# Protect.net
KiCad netlist of a schematic drawn in Altium Designer
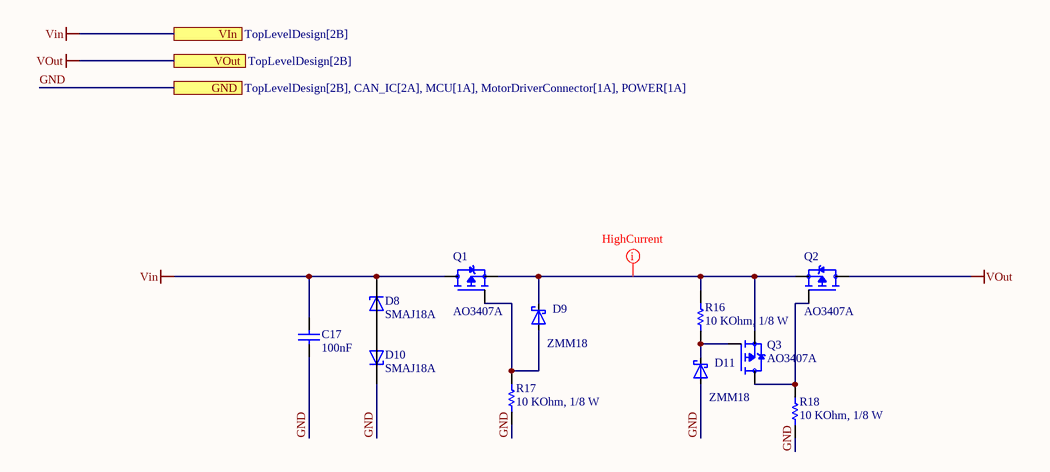
[diagram p0: Protect.SchDoc]

(export (version "E")
  (design (tool "Eeschema 10.0.6"))
  (components
    (comp (ref "C17")
      (value "100nF")
      (footprint "CAP_0805")
      (description "CAP, size 0805, 0.1 nF, 50 VDC")
      (fields
        (field (name "TOLERANCE") "10%")
        (field (name "Comment") "0108051041050")
        (field (name "SOURCE") "Capacitor_0805_10_percent.SchLib")
      )
      (libsource (lib "Tin Tran") (part "0108056841050"))
    )
    (comp (ref "D8")
      (value "SMAJ18A")
      (footprint "DIOM4325X250N")
      (description "400W, 21.1V, 5%, Unidirectional, TVS")
      (fields (field (name "MF") "Taiwan Semiconductor"))
      (libsource (lib "Tin Tran") (part "SMAJ18A"))
    )
    (comp (ref "D9")
      (value "ZMM18")
      (footprint "SOD-80_MiniMELF_Glass")
      (libsource (lib "Tin Tran") (part "Schottky-Diode"))
    )
    (comp (ref "D10")
      (value "SMAJ18A")
      (footprint "DIOM4325X250N")
      (description "400W, 21.1V, 5%, Unidirectional, TVS")
      (fields (field (name "MF") "Taiwan Semiconductor"))
      (libsource (lib "Tin Tran") (part "SMAJ18A"))
    )
    (comp (ref "D11")
      (value "ZMM18")
      (footprint "SOD-80_MiniMELF_Glass")
      (libsource (lib "Tin Tran") (part "Schottky-Diode"))
    )
    (comp (ref "Q1")
      (value "AO3407A")
      (footprint "SOT95P280X125-3N")
      (description "P-Channel 30 V 4.3A (Ta) 1.4W (Ta) Surface Mount SOT-23-3")
      (fields (field (name "MF") "Alpha &"))
      (libsource (lib "Tin Tran") (part "AO3407A"))
    )
    (comp (ref "Q2")
      (value "AO3407A")
      (footprint "SOT95P280X125-3N")
      (description "P-Channel 30 V 4.3A (Ta) 1.4W (Ta) Surface Mount SOT-23-3")
      (fields (field (name "MF") "Alpha &"))
      (libsource (lib "Tin Tran") (part "AO3407A"))
    )
    (comp (ref "Q3")
      (value "AO3407A")
      (footprint "SOT95P280X125-3N")
      (description "P-Channel 30 V 4.3A (Ta) 1.4W (Ta) Surface Mount SOT-23-3")
      (fields (field (name "MF") "Alpha &"))
      (libsource (lib "Tin Tran") (part "AO3407A"))
    )
    (comp (ref "R16")
      (value "10 KOhm, 1/8 W")
      (footprint "RESISTOR_0805")
      (description "RES, size 0805, 10 KOhm, 1/8 W")
      (fields (field (name "Comment") "0008051031"))
      (libsource (lib "Tin Tran") (part "0008052035_1"))
    )
    (comp (ref "R17")
      (value "10 KOhm, 1/8 W")
      (footprint "RESISTOR_0805")
      (description "RES, size 0805, 10 KOhm, 1/8 W")
      (fields (field (name "Comment") "0008051031"))
      (libsource (lib "Tin Tran") (part "0008052035_1"))
    )
    (comp (ref "R18")
      (value "10 KOhm, 1/8 W")
      (footprint "RESISTOR_0805")
      (description "RES, size 0805, 10 KOhm, 1/8 W")
      (fields (field (name "Comment") "0008051031"))
      (libsource (lib "Tin Tran") (part "0008052035_1"))
    )
  )
  (nets
    (net (code "1") (name "/GND") (class "Default")
      (node (ref "C17") (pin "1") (pinfunction "1_1") (pintype "passive"))
      (node (ref "D10") (pin "C") (pinfunction "C_C") (pintype "passive"))
      (node (ref "D11") (pin "A") (pinfunction "A_A") (pintype "passive"))
      (node (ref "R17") (pin "1") (pinfunction "1_1") (pintype "passive"))
      (node (ref "R18") (pin "1") (pinfunction "1_1") (pintype "passive"))
    )
    (net (code "2") (name "Net-(D10-PadA)") (class "Default")
      (node (ref "D10") (pin "A") (pinfunction "A_A") (pintype "passive"))
      (node (ref "D8") (pin "A") (pinfunction "A_A") (pintype "passive"))
    )
    (net (code "3") (name "Net-(Q1-G)") (class "Default")
      (node (ref "D9") (pin "A") (pinfunction "A_A") (pintype "passive"))
      (node (ref "Q1") (pin "1") (pinfunction "G_1") (pintype "passive"))
      (node (ref "R17") (pin "2") (pinfunction "2_2") (pintype "passive"))
    )
    (net (code "4") (name "Net-(Q1-S)") (class "Default")
      (node (ref "D9") (pin "K") (pinfunction "K_K") (pintype "passive"))
      (node (ref "Q1") (pin "2") (pinfunction "S_2") (pintype "passive"))
      (node (ref "Q2") (pin "2") (pinfunction "S_2") (pintype "passive"))
      (node (ref "Q3") (pin "2") (pinfunction "S_2") (pintype "passive"))
      (node (ref "R16") (pin "2") (pinfunction "2_2") (pintype "passive"))
    )
    (net (code "5") (name "Net-(Q2-G)") (class "Default")
      (node (ref "Q2") (pin "1") (pinfunction "G_1") (pintype "passive"))
      (node (ref "Q3") (pin "3") (pinfunction "D_3") (pintype "passive"))
      (node (ref "R18") (pin "2") (pinfunction "2_2") (pintype "passive"))
    )
    (net (code "6") (name "Net-(Q3-G)") (class "Default")
      (node (ref "D11") (pin "K") (pinfunction "K_K") (pintype "passive"))
      (node (ref "Q3") (pin "1") (pinfunction "G_1") (pintype "passive"))
      (node (ref "R16") (pin "1") (pinfunction "1_1") (pintype "passive"))
    )
    (net (code "7") (name "VOut") (class "Default")
      (node (ref "Q2") (pin "3") (pinfunction "D_3") (pintype "passive"))
    )
    (net (code "8") (name "Vin") (class "Default")
      (node (ref "C17") (pin "2") (pinfunction "2_2") (pintype "passive"))
      (node (ref "D8") (pin "C") (pinfunction "C_C") (pintype "passive"))
      (node (ref "Q1") (pin "3") (pinfunction "D_3") (pintype "passive"))
    )
  )
)
